# sm32_sx1278.net
KiCad netlist of a schematic drawn in Altium Designer
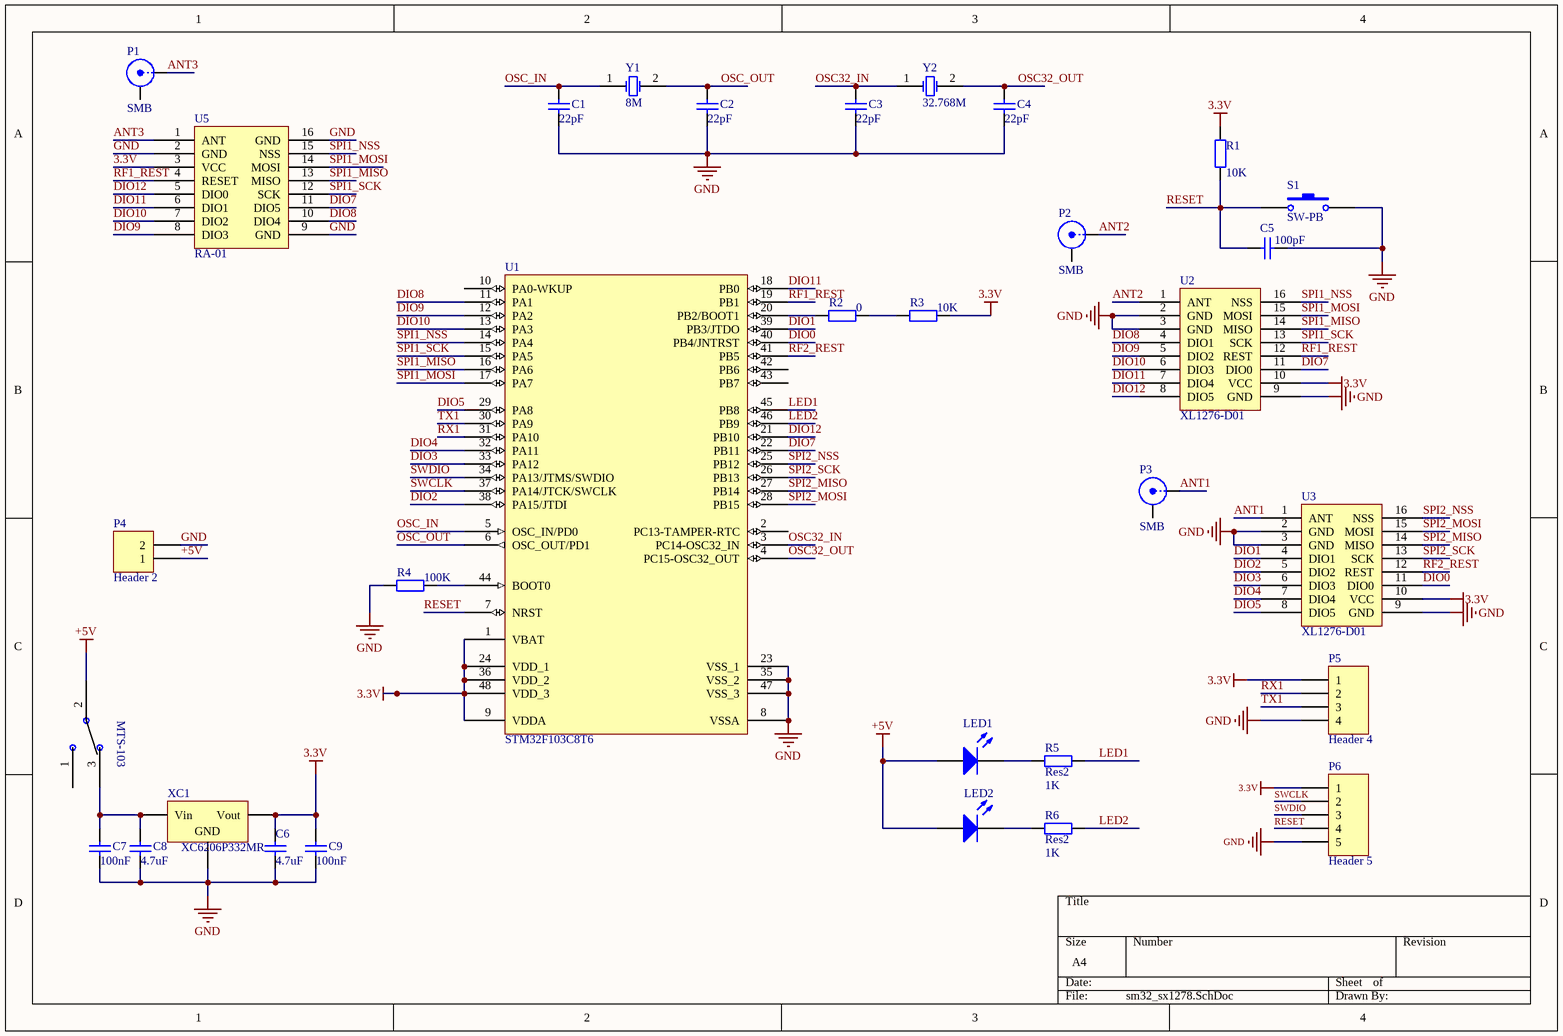
[diagram p0: sm32_sx1278.SchDoc]

(export (version "E")
  (design (tool "Eeschema 10.0.6"))
  (components
    (comp (ref "C1")
      (value "22pF")
      (footprint "1608[0603]")
      (description "Capacitor (Semiconductor SIM Model)")
      (fields (field (name "Comment") "Cap Semi") (field (name "PUBLISHER") "Altium Limited"))
      (libsource (lib "Miscellaneous Devices") (part "Cap Semi"))
    )
    (comp (ref "C2")
      (value "22pF")
      (footprint "1608[0603]")
      (description "Capacitor (Semiconductor SIM Model)")
      (fields (field (name "Comment") "Cap Semi") (field (name "PUBLISHER") "Altium Limited"))
      (libsource (lib "Miscellaneous Devices") (part "Cap Semi"))
    )
    (comp (ref "C3")
      (value "22pF")
      (footprint "1608[0603]")
      (description "Capacitor (Semiconductor SIM Model)")
      (fields (field (name "Comment") "Cap Semi") (field (name "PUBLISHER") "Altium Limited"))
      (libsource (lib "Miscellaneous Devices") (part "Cap Semi"))
    )
    (comp (ref "C4")
      (value "22pF")
      (footprint "1608[0603]")
      (description "Capacitor (Semiconductor SIM Model)")
      (fields (field (name "Comment") "Cap Semi") (field (name "PUBLISHER") "Altium Limited"))
      (libsource (lib "Miscellaneous Devices") (part "Cap Semi"))
    )
    (comp (ref "C5")
      (value "100pF")
      (footprint "1608[0603]")
      (description "Capacitor (Semiconductor SIM Model)")
      (fields (field (name "Comment") "Cap Semi") (field (name "PUBLISHER") "Altium Limited"))
      (libsource (lib "Miscellaneous Devices") (part "Cap Semi"))
    )
    (comp (ref "C6")
      (value "4.7uF")
      (footprint "1608[0603]")
      (description "Capacitor (Semiconductor SIM Model)")
      (fields (field (name "Comment") "Cap Semi") (field (name "PUBLISHER") "Altium Limited"))
      (libsource (lib "Miscellaneous Devices") (part "Cap Semi"))
    )
    (comp (ref "C7")
      (value "100nF")
      (footprint "1608[0603]")
      (description "Capacitor (Semiconductor SIM Model)")
      (fields (field (name "Comment") "Cap Semi") (field (name "PUBLISHER") "Altium Limited"))
      (libsource (lib "Miscellaneous Devices") (part "Cap Semi"))
    )
    (comp (ref "C8")
      (value "4.7uF")
      (footprint "1608[0603]")
      (description "Capacitor (Semiconductor SIM Model)")
      (fields (field (name "Comment") "Cap Semi") (field (name "PUBLISHER") "Altium Limited"))
      (libsource (lib "Miscellaneous Devices") (part "Cap Semi"))
    )
    (comp (ref "C9")
      (value "100nF")
      (footprint "1608[0603]")
      (description "Capacitor (Semiconductor SIM Model)")
      (fields (field (name "Comment") "Cap Semi") (field (name "PUBLISHER") "Altium Limited"))
      (libsource (lib "Miscellaneous Devices") (part "Cap Semi"))
    )
    (comp (ref "LED1")
      (value "LED2")
      (footprint "3.2X1.6X1.1")
      (description "Typical RED, GREEN, YELLOW, AMBER GaAs LED")
      (fields (field (name "PUBLISHER") "Altium Limited"))
      (libsource (lib "Miscellaneous Devices") (part "LED2"))
    )
    (comp (ref "LED2")
      (value "LED2")
      (footprint "3.2X1.6X1.1")
      (description "Typical RED, GREEN, YELLOW, AMBER GaAs LED")
      (fields (field (name "PUBLISHER") "Altium Limited"))
      (libsource (lib "Miscellaneous Devices") (part "LED2"))
    )
    (comp (ref "MTS-1")
      (value "MTS-103")
      (footprint "PcbLib1:MTS-103")
      (libsource (lib "Schlib1") (part "MTS-103"))
    )
    (comp (ref "P1")
      (value "SMB")
      (footprint "SMB1")
      (description "SMB Straight Connector")
      (fields (field (name "PUBLISHER") "Altium Limited"))
      (libsource (lib "Miscellaneous Connectors") (part "SMB"))
    )
    (comp (ref "P2")
      (value "SMB")
      (footprint "SMB1")
      (description "SMB Straight Connector")
      (fields (field (name "PUBLISHER") "Altium Limited"))
      (libsource (lib "Miscellaneous Connectors") (part "SMB"))
    )
    (comp (ref "P3")
      (value "SMB")
      (footprint "SMB1")
      (description "SMB Straight Connector")
      (fields (field (name "PUBLISHER") "Altium Limited"))
      (libsource (lib "Miscellaneous Connectors") (part "SMB"))
    )
    (comp (ref "P4")
      (value "Header 2")
      (footprint "HDR1X2")
      (description "Header, 2-Pin")
      (fields (field (name "PUBLISHER") "Altium Limited"))
      (libsource (lib "Miscellaneous Connectors") (part "Header 2"))
    )
    (comp (ref "P5")
      (value "Header 4")
      (footprint "HDR1X4")
      (description "Header, 4-Pin")
      (fields (field (name "PUBLISHER") "Altium Limited"))
      (libsource (lib "Miscellaneous Connectors") (part "Header 4"))
    )
    (comp (ref "P6")
      (value "Header 5")
      (footprint "HDR1X5")
      (description "Header, 5-Pin")
      (fields (field (name "PUBLISHER") "Altium Limited"))
      (libsource (lib "Miscellaneous Connectors") (part "Header 5"))
    )
    (comp (ref "R1")
      (value "10K")
      (footprint "1608[0603]")
      (description "Resistor")
      (fields (field (name "Comment") "Res2") (field (name "PUBLISHER") "Altium Limited"))
      (libsource (lib "") (part "Res2_1"))
    )
    (comp (ref "R2")
      (value "0")
      (footprint "1608[0603]")
      (description "Resistor")
      (fields (field (name "Comment") "Res2") (field (name "PUBLISHER") "Altium Limited"))
      (libsource (lib "Miscellaneous Devices") (part "Res2"))
    )
    (comp (ref "R3")
      (value "10K")
      (footprint "1608[0603]")
      (description "Resistor")
      (fields (field (name "Comment") "Res2") (field (name "PUBLISHER") "Altium Limited"))
      (libsource (lib "Miscellaneous Devices") (part "Res2"))
    )
    (comp (ref "R4")
      (value "100K")
      (footprint "1608[0603]")
      (description "Resistor")
      (fields (field (name "Comment") "Res2") (field (name "PUBLISHER") "Altium Limited"))
      (libsource (lib "Miscellaneous Devices") (part "Res2"))
    )
    (comp (ref "R5")
      (value "Res2")
      (footprint "1608[0603]")
      (description "Resistor")
      (fields (field (name "ALTIUM_VALUE") "1K") (field (name "PUBLISHER") "Altium Limited"))
      (libsource (lib "Miscellaneous Devices") (part "Res2"))
    )
    (comp (ref "R6")
      (value "Res2")
      (footprint "1608[0603]")
      (description "Resistor")
      (fields (field (name "ALTIUM_VALUE") "1K") (field (name "PUBLISHER") "Altium Limited"))
      (libsource (lib "Miscellaneous Devices") (part "Res2"))
    )
    (comp (ref "S1")
      (value "SW-PB")
      (footprint "SPST-2")
      (description "Switch")
      (fields (field (name "PUBLISHER") "Altium Limited"))
      (libsource (lib "Miscellaneous Devices") (part "SW-PB"))
    )
    (comp (ref "U1")
      (value "STM32F103C8T6")
      (footprint "LQFP48_N")
      (description "STM32 ARM-based 32-bit MCU with 64 Kbytes Flash, 48-pin LQFP, Industrial Temperature")
      (fields (field (name "PUBLISHER") "Altium Limited"))
      (libsource (lib "ST Microcontroller 32-Bit STM32") (part "STM32F103C8T6"))
    )
    (comp (ref "U2")
      (value "XL1276-D01")
      (footprint "XL1278-DO1")
      (libsource (lib "Schlib1") (part "XL1276-D01"))
    )
    (comp (ref "U3")
      (value "XL1276-D01")
      (footprint "XL1278-DO1")
      (libsource (lib "Schlib1") (part "XL1276-D01"))
    )
    (comp (ref "U5") (value "RA-01") (footprint "Ra-01") (libsource (lib "Schlib1") (part "RA-01")))
    (comp (ref "XC1")
      (value "XC6206P332MR")
      (footprint "SOT89L")
      (description "Voltage Regulator")
      (fields (field (name "PUBLISHER") "Altium Limited"))
      (libsource (lib "Miscellaneous Devices") (part "Volt Reg"))
    )
    (comp (ref "Y1")
      (value "8M")
      (footprint "HC-48SMD")
      (description "Crystal Oscillator")
      (fields (field (name "PUBLISHER") "Altium Limited"))
      (libsource (lib "Miscellaneous Devices") (part "XTAL"))
    )
    (comp (ref "Y2")
      (value "32.768M")
      (footprint "FC135")
      (description "Crystal Oscillator")
      (fields (field (name "PUBLISHER") "Altium Limited"))
      (libsource (lib "Miscellaneous Devices") (part "XTAL"))
    )
  )
  (nets
    (net (code "1") (name "+5V") (class "Default")
      (node (ref "LED1") (pin "1") (pinfunction "A_1") (pintype "passive"))
      (node (ref "LED2") (pin "1") (pinfunction "A_1") (pintype "passive"))
      (node (ref "MTS-1") (pin "2") (pinfunction "2_2") (pintype "passive"))
      (node (ref "P4") (pin "1") (pinfunction "1_1") (pintype "passive"))
    )
    (net (code "2") (name "/ANT1") (class "Default")
      (node (ref "P3") (pin "1") (pinfunction "X_1") (pintype "passive"))
      (node (ref "U3") (pin "1") (pinfunction "ANT_1") (pintype "passive"))
    )
    (net (code "3") (name "/ANT2") (class "Default")
      (node (ref "P2") (pin "1") (pinfunction "X_1") (pintype "passive"))
      (node (ref "U2") (pin "1") (pinfunction "ANT_1") (pintype "passive"))
    )
    (net (code "4") (name "/ANT3") (class "Default")
      (node (ref "P1") (pin "1") (pinfunction "X_1") (pintype "passive"))
      (node (ref "U5") (pin "1") (pinfunction "ANT_1") (pintype "passive"))
    )
    (net (code "5") (name "/DIO0") (class "Default")
      (node (ref "U1") (pin "40") (pinfunction "PB4/JNTRST_40") (pintype "bidirectional"))
      (node (ref "U3") (pin "11") (pinfunction "DIO0_11") (pintype "passive"))
    )
    (net (code "6") (name "/DIO1") (class "Default")
      (node (ref "U1") (pin "39") (pinfunction "PB3/JTDO_39") (pintype "bidirectional"))
      (node (ref "U3") (pin "4") (pinfunction "DIO1_4") (pintype "passive"))
    )
    (net (code "7") (name "/DIO2") (class "Default")
      (node (ref "U1") (pin "38") (pinfunction "PA15/JTDI_38") (pintype "bidirectional"))
      (node (ref "U3") (pin "5") (pinfunction "DIO2_5") (pintype "passive"))
    )
    (net (code "8") (name "/DIO3") (class "Default")
      (node (ref "U1") (pin "33") (pinfunction "PA12_33") (pintype "bidirectional"))
      (node (ref "U3") (pin "6") (pinfunction "DIO3_6") (pintype "passive"))
    )
    (net (code "9") (name "/DIO4") (class "Default")
      (node (ref "U1") (pin "32") (pinfunction "PA11_32") (pintype "bidirectional"))
      (node (ref "U3") (pin "7") (pinfunction "DIO4_7") (pintype "passive"))
    )
    (net (code "10") (name "/DIO5") (class "Default")
      (node (ref "U1") (pin "29") (pinfunction "PA8_29") (pintype "bidirectional"))
      (node (ref "U3") (pin "8") (pinfunction "DIO5_8") (pintype "passive"))
    )
    (net (code "11") (name "/DIO7") (class "Default")
      (node (ref "U1") (pin "22") (pinfunction "PB11_22") (pintype "bidirectional"))
      (node (ref "U2") (pin "11") (pinfunction "DIO0_11") (pintype "passive"))
      (node (ref "U5") (pin "11") (pinfunction "DIO5_11") (pintype "passive"))
    )
    (net (code "12") (name "/DIO8") (class "Default")
      (node (ref "U1") (pin "11") (pinfunction "PA1_11") (pintype "bidirectional"))
      (node (ref "U2") (pin "4") (pinfunction "DIO1_4") (pintype "passive"))
      (node (ref "U5") (pin "10") (pinfunction "DIO4_10") (pintype "passive"))
    )
    (net (code "13") (name "/DIO9") (class "Default")
      (node (ref "U1") (pin "12") (pinfunction "PA2_12") (pintype "bidirectional"))
      (node (ref "U2") (pin "5") (pinfunction "DIO2_5") (pintype "passive"))
      (node (ref "U5") (pin "8") (pinfunction "DIO3_8") (pintype "passive"))
    )
    (net (code "14") (name "/DIO10") (class "Default")
      (node (ref "U1") (pin "13") (pinfunction "PA3_13") (pintype "bidirectional"))
      (node (ref "U2") (pin "6") (pinfunction "DIO3_6") (pintype "passive"))
      (node (ref "U5") (pin "7") (pinfunction "DIO2_7") (pintype "passive"))
    )
    (net (code "15") (name "/DIO11") (class "Default")
      (node (ref "U1") (pin "18") (pinfunction "PB0_18") (pintype "bidirectional"))
      (node (ref "U2") (pin "7") (pinfunction "DIO4_7") (pintype "passive"))
      (node (ref "U5") (pin "6") (pinfunction "DIO1_6") (pintype "passive"))
    )
    (net (code "16") (name "/DIO12") (class "Default")
      (node (ref "U1") (pin "21") (pinfunction "PB10_21") (pintype "bidirectional"))
      (node (ref "U2") (pin "8") (pinfunction "DIO5_8") (pintype "passive"))
      (node (ref "U5") (pin "5") (pinfunction "DIO0_5") (pintype "passive"))
    )
    (net (code "17") (name "/LED1") (class "Default")
      (node (ref "R5") (pin "2") (pinfunction "2_2") (pintype "passive"))
      (node (ref "U1") (pin "45") (pinfunction "PB8_45") (pintype "bidirectional"))
    )
    (net (code "18") (name "/LED2") (class "Default")
      (node (ref "R6") (pin "2") (pinfunction "2_2") (pintype "passive"))
      (node (ref "U1") (pin "46") (pinfunction "PB9_46") (pintype "bidirectional"))
    )
    (net (code "19") (name "/OSC32_IN") (class "Default")
      (node (ref "C3") (pin "2") (pinfunction "2_2") (pintype "passive"))
      (node (ref "U1") (pin "3") (pinfunction "PC14-OSC32_IN_3") (pintype "bidirectional"))
      (node (ref "Y2") (pin "1") (pinfunction "OSC1_1") (pintype "passive"))
    )
    (net (code "20") (name "/OSC32_OUT") (class "Default")
      (node (ref "C4") (pin "2") (pinfunction "2_2") (pintype "passive"))
      (node (ref "U1") (pin "4") (pinfunction "PC15-OSC32_OUT_4") (pintype "bidirectional"))
      (node (ref "Y2") (pin "2") (pinfunction "OSC2_2") (pintype "passive"))
    )
    (net (code "21") (name "/OSC_IN") (class "Default")
      (node (ref "C1") (pin "2") (pinfunction "2_2") (pintype "passive"))
      (node (ref "U1") (pin "5") (pinfunction "OSC_IN/PD0_5") (pintype "input"))
      (node (ref "Y1") (pin "1") (pinfunction "OSC1_1") (pintype "passive"))
    )
    (net (code "22") (name "/OSC_OUT") (class "Default")
      (node (ref "C2") (pin "2") (pinfunction "2_2") (pintype "passive"))
      (node (ref "U1") (pin "6") (pinfunction "OSC_OUT/PD1_6") (pintype "output"))
      (node (ref "Y1") (pin "2") (pinfunction "OSC2_2") (pintype "passive"))
    )
    (net (code "23") (name "/RESET") (class "Default")
      (node (ref "C5") (pin "1") (pinfunction "1_1") (pintype "passive"))
      (node (ref "P6") (pin "4") (pinfunction "4_4") (pintype "passive"))
      (node (ref "R1") (pin "2") (pinfunction "2_2") (pintype "passive"))
      (node (ref "S1") (pin "1") (pinfunction "1_1") (pintype "passive"))
      (node (ref "U1") (pin "7") (pinfunction "NRST_7") (pintype "bidirectional"))
    )
    (net (code "24") (name "/RF1_REST") (class "Default")
      (node (ref "U1") (pin "19") (pinfunction "PB1_19") (pintype "bidirectional"))
      (node (ref "U2") (pin "12") (pinfunction "REST_12") (pintype "passive"))
      (node (ref "U5") (pin "4") (pinfunction "RESET_4") (pintype "passive"))
    )
    (net (code "25") (name "/RF2_REST") (class "Default")
      (node (ref "U1") (pin "41") (pinfunction "PB5_41") (pintype "bidirectional"))
      (node (ref "U3") (pin "12") (pinfunction "REST_12") (pintype "passive"))
    )
    (net (code "26") (name "/RX1") (class "Default")
      (node (ref "P5") (pin "2") (pinfunction "2_2") (pintype "passive"))
      (node (ref "U1") (pin "31") (pinfunction "PA10_31") (pintype "bidirectional"))
    )
    (net (code "27") (name "/SPI1_MISO") (class "Default")
      (node (ref "U1") (pin "16") (pinfunction "PA6_16") (pintype "bidirectional"))
      (node (ref "U2") (pin "14") (pinfunction "MISO_14") (pintype "passive"))
      (node (ref "U5") (pin "13") (pinfunction "MISO_13") (pintype "passive"))
    )
    (net (code "28") (name "/SPI1_MOSI") (class "Default")
      (node (ref "U1") (pin "17") (pinfunction "PA7_17") (pintype "bidirectional"))
      (node (ref "U2") (pin "15") (pinfunction "MOSI_15") (pintype "passive"))
      (node (ref "U5") (pin "14") (pinfunction "MOSI_14") (pintype "passive"))
    )
    (net (code "29") (name "/SPI1_NSS") (class "Default")
      (node (ref "U1") (pin "14") (pinfunction "PA4_14") (pintype "bidirectional"))
      (node (ref "U2") (pin "16") (pinfunction "NSS_16") (pintype "passive"))
      (node (ref "U5") (pin "15") (pinfunction "NSS_15") (pintype "passive"))
    )
    (net (code "30") (name "/SPI1_SCK") (class "Default")
      (node (ref "U1") (pin "15") (pinfunction "PA5_15") (pintype "bidirectional"))
      (node (ref "U2") (pin "13") (pinfunction "SCK_13") (pintype "passive"))
      (node (ref "U5") (pin "12") (pinfunction "SCK_12") (pintype "passive"))
    )
    (net (code "31") (name "/SPI2_MISO") (class "Default")
      (node (ref "U1") (pin "27") (pinfunction "PB14_27") (pintype "bidirectional"))
      (node (ref "U3") (pin "14") (pinfunction "MISO_14") (pintype "passive"))
    )
    (net (code "32") (name "/SPI2_MOSI") (class "Default")
      (node (ref "U1") (pin "28") (pinfunction "PB15_28") (pintype "bidirectional"))
      (node (ref "U3") (pin "15") (pinfunction "MOSI_15") (pintype "passive"))
    )
    (net (code "33") (name "/SPI2_NSS") (class "Default")
      (node (ref "U1") (pin "25") (pinfunction "PB12_25") (pintype "bidirectional"))
      (node (ref "U3") (pin "16") (pinfunction "NSS_16") (pintype "passive"))
    )
    (net (code "34") (name "/SPI2_SCK") (class "Default")
      (node (ref "U1") (pin "26") (pinfunction "PB13_26") (pintype "bidirectional"))
      (node (ref "U3") (pin "13") (pinfunction "SCK_13") (pintype "passive"))
    )
    (net (code "35") (name "/SWCLK") (class "Default")
      (node (ref "P6") (pin "2") (pinfunction "2_2") (pintype "passive"))
      (node (ref "U1") (pin "37") (pinfunction "PA14/JTCK/SWCLK_37") (pintype "bidirectional"))
    )
    (net (code "36") (name "/SWDIO") (class "Default")
      (node (ref "P6") (pin "3") (pinfunction "3_3") (pintype "passive"))
      (node (ref "U1") (pin "34") (pinfunction "PA13/JTMS/SWDIO_34") (pintype "bidirectional"))
    )
    (net (code "37") (name "/TX1") (class "Default")
      (node (ref "P5") (pin "3") (pinfunction "3_3") (pintype "passive"))
      (node (ref "U1") (pin "30") (pinfunction "PA9_30") (pintype "bidirectional"))
    )
    (net (code "38") (name "3.3V") (class "Default")
      (node (ref "C6") (pin "2") (pinfunction "2_2") (pintype "passive"))
      (node (ref "C9") (pin "2") (pinfunction "2_2") (pintype "passive"))
      (node (ref "P5") (pin "1") (pinfunction "1_1") (pintype "passive"))
      (node (ref "P6") (pin "1") (pinfunction "1_1") (pintype "passive"))
      (node (ref "R1") (pin "1") (pinfunction "1_1") (pintype "passive"))
      (node (ref "R3") (pin "2") (pinfunction "2_2") (pintype "passive"))
      (node (ref "U1") (pin "1") (pinfunction "VBAT_1") (pintype "power_in"))
      (node (ref "U1") (pin "24") (pinfunction "VDD_1_24") (pintype "power_in"))
      (node (ref "U1") (pin "36") (pinfunction "VDD_2_36") (pintype "power_in"))
      (node (ref "U1") (pin "48") (pinfunction "VDD_3_48") (pintype "power_in"))
      (node (ref "U1") (pin "9") (pinfunction "VDDA_9") (pintype "power_in"))
      (node (ref "U2") (pin "10") (pinfunction "VCC_10") (pintype "passive"))
      (node (ref "U3") (pin "10") (pinfunction "VCC_10") (pintype "passive"))
      (node (ref "U5") (pin "3") (pinfunction "VCC_3") (pintype "passive"))
      (node (ref "XC1") (pin "3") (pinfunction "Vout_3") (pintype "passive"))
    )
    (net (code "39") (name "GND") (class "Default")
      (node (ref "C1") (pin "1") (pinfunction "1_1") (pintype "passive"))
      (node (ref "C2") (pin "1") (pinfunction "1_1") (pintype "passive"))
      (node (ref "C3") (pin "1") (pinfunction "1_1") (pintype "passive"))
      (node (ref "C4") (pin "1") (pinfunction "1_1") (pintype "passive"))
      (node (ref "C5") (pin "2") (pinfunction "2_2") (pintype "passive"))
      (node (ref "C6") (pin "1") (pinfunction "1_1") (pintype "passive"))
      (node (ref "C7") (pin "1") (pinfunction "1_1") (pintype "passive"))
      (node (ref "C8") (pin "1") (pinfunction "1_1") (pintype "passive"))
      (node (ref "C9") (pin "1") (pinfunction "1_1") (pintype "passive"))
      (node (ref "P4") (pin "2") (pinfunction "2_2") (pintype "passive"))
      (node (ref "P5") (pin "4") (pinfunction "4_4") (pintype "passive"))
      (node (ref "P6") (pin "5") (pinfunction "5_5") (pintype "passive"))
      (node (ref "R4") (pin "1") (pinfunction "1_1") (pintype "passive"))
      (node (ref "S1") (pin "2") (pinfunction "2_2") (pintype "passive"))
      (node (ref "U1") (pin "23") (pinfunction "VSS_1_23") (pintype "power_in"))
      (node (ref "U1") (pin "35") (pinfunction "VSS_2_35") (pintype "power_in"))
      (node (ref "U1") (pin "47") (pinfunction "VSS_3_47") (pintype "power_in"))
      (node (ref "U1") (pin "8") (pinfunction "VSSA_8") (pintype "power_in"))
      (node (ref "U2") (pin "2") (pinfunction "GND_2") (pintype "passive"))
      (node (ref "U2") (pin "3") (pinfunction "GND_3") (pintype "passive"))
      (node (ref "U2") (pin "9") (pinfunction "GND_9") (pintype "passive"))
      (node (ref "U3") (pin "2") (pinfunction "GND_2") (pintype "passive"))
      (node (ref "U3") (pin "3") (pinfunction "GND_3") (pintype "passive"))
      (node (ref "U3") (pin "9") (pinfunction "GND_9") (pintype "passive"))
      (node (ref "U5") (pin "16") (pinfunction "GND_16") (pintype "passive"))
      (node (ref "U5") (pin "2") (pinfunction "GND_2") (pintype "passive"))
      (node (ref "U5") (pin "9") (pinfunction "GND_9") (pintype "passive"))
      (node (ref "XC1") (pin "2") (pinfunction "GND_2") (pintype "passive"))
    )
    (net (code "40") (name "Net-(LED1-K)") (class "Default")
      (node (ref "LED1") (pin "2") (pinfunction "K_2") (pintype "passive"))
      (node (ref "R5") (pin "1") (pinfunction "1_1") (pintype "passive"))
    )
    (net (code "41") (name "Net-(LED2-K)") (class "Default")
      (node (ref "LED2") (pin "2") (pinfunction "K_2") (pintype "passive"))
      (node (ref "R6") (pin "1") (pinfunction "1_1") (pintype "passive"))
    )
    (net (code "42") (name "Net-(R2-Pad2)") (class "Default")
      (node (ref "R2") (pin "2") (pinfunction "2_2") (pintype "passive"))
      (node (ref "R3") (pin "1") (pinfunction "1_1") (pintype "passive"))
    )
    (net (code "43") (name "Net-(U1-BOOT0)") (class "Default")
      (node (ref "R4") (pin "2") (pinfunction "2_2") (pintype "passive"))
      (node (ref "U1") (pin "44") (pinfunction "BOOT0_44") (pintype "input"))
    )
    (net (code "44") (name "Net-(U1-PB2{slash}BOOT1)") (class "Default")
      (node (ref "R2") (pin "1") (pinfunction "1_1") (pintype "passive"))
      (node (ref "U1") (pin "20") (pinfunction "PB2/BOOT1_20") (pintype "bidirectional"))
    )
    (net (code "45") (name "Net-(XC1-Vin)") (class "Default")
      (node (ref "C7") (pin "2") (pinfunction "2_2") (pintype "passive"))
      (node (ref "C8") (pin "2") (pinfunction "2_2") (pintype "passive"))
      (node (ref "MTS-1") (pin "3") (pinfunction "3_3") (pintype "passive"))
      (node (ref "XC1") (pin "1") (pinfunction "Vin_1") (pintype "passive"))
    )
    (net (code "46") (name "unconnected-(MTS-1-Pad1)") (class "Default")
      (node (ref "MTS-1") (pin "1") (pinfunction "1_1") (pintype "passive"))
    )
    (net (code "47") (name "unconnected-(P1-Y-Pad2)") (class "Default")
      (node (ref "P1") (pin "2") (pinfunction "Y_2") (pintype "passive"))
    )
    (net (code "48") (name "unconnected-(P2-Y-Pad2)") (class "Default")
      (node (ref "P2") (pin "2") (pinfunction "Y_2") (pintype "passive"))
    )
    (net (code "49") (name "unconnected-(P3-Y-Pad2)") (class "Default")
      (node (ref "P3") (pin "2") (pinfunction "Y_2") (pintype "passive"))
    )
    (net (code "50") (name "unconnected-(U1-PA0-WKUP-Pad10)") (class "Default")
      (node (ref "U1") (pin "10") (pinfunction "PA0-WKUP_10") (pintype "bidirectional"))
    )
    (net (code "51") (name "unconnected-(U1-PB6-Pad42)") (class "Default")
      (node (ref "U1") (pin "42") (pinfunction "PB6_42") (pintype "bidirectional"))
    )
    (net (code "52") (name "unconnected-(U1-PB7-Pad43)") (class "Default")
      (node (ref "U1") (pin "43") (pinfunction "PB7_43") (pintype "bidirectional"))
    )
    (net (code "53") (name "unconnected-(U1-PC13-TAMPER-RTC-Pad2)") (class "Default")
      (node (ref "U1") (pin "2") (pinfunction "PC13-TAMPER-RTC_2") (pintype "bidirectional"))
    )
  )
)
